# Buck_Power.net
KiCad netlist of a schematic drawn in Altium Designer
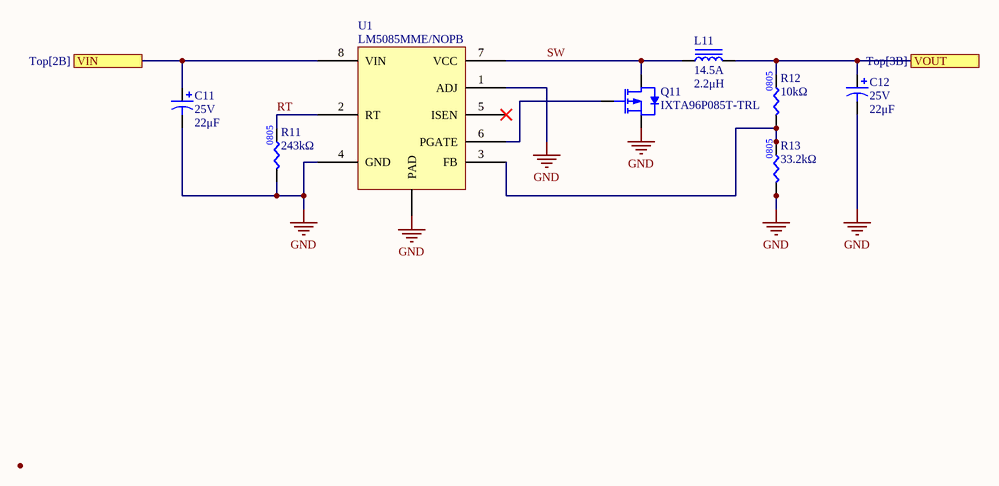
[diagram p0: Buck Power.SchDoc]

(export (version "E")
  (design (tool "Eeschema 10.0.6"))
  (components
    (comp (ref "C11")
      (value "22μF")
      (footprint "CAP2917")
      (description "CAP TANT 22UF 20% 25V 2917")
      (fields (field (name "VOLTAGE RATING") "25V") (field (name "Comment") "CAP_22uF_25V_TANT"))
      (libsource (lib "UWRT_Schematic_Library_2020") (part "CAP_22uF_25V_TANT"))
    )
    (comp (ref "C12")
      (value "22μF")
      (footprint "CAP2917")
      (description "CAP TANT 22UF 20% 25V 2917")
      (fields (field (name "VOLTAGE RATING") "25V") (field (name "Comment") "CAP_22uF_25V_TANT"))
      (libsource (lib "UWRT_Schematic_Library_2020") (part "CAP_22uF_25V_TANT"))
    )
    (comp (ref "L11")
      (value "IND_2.2uH_14.5A")
      (footprint "IND_VISHAY_IHLP3232DZER2R2M11")
      (description "INDUCTOR 2.2UH 14.5A 9.41 MOHM")
      (fields (field (name "CURRENT RATING") "14.5A") (field (name "INDUCTANCE") "2.2μH"))
      (libsource (lib "UWRT_Schematic_Library_2020") (part "IND_2.2uH_14.5A"))
    )
    (comp (ref "Q11")
      (value "PMOS_85V_96A")
      (footprint "D-PAK")
      (description "MOSFET P-CH 85V 96A TO263")
      (fields (field (name "MANUFACTURER PART NUMBER 1") "IXTA96P085T-TRL"))
      (libsource (lib "UWRT_Schematic_Library_2020") (part "PMOS_85V_96A"))
    )
    (comp (ref "R11")
      (value "243kΩ")
      (footprint "RES0805")
      (description "RES 243K OHM 1% 1/8W 0805")
      (fields (field (name "Comment") "RES_243kΩ_0805_1%"))
      (libsource (lib "UWRT_Schematic_Library_2020") (part "RES_243kΩ_0805_1%"))
    )
    (comp (ref "R12")
      (value "10kΩ")
      (footprint "RES0805")
      (description "RES 10K OHM 5% 1/8W 0805")
      (fields (field (name "LCSC PART #") "C17414") (field (name "Comment") "RES_10kΩ_0805_5%"))
      (libsource (lib "UWRT_Schematic_Library_2020") (part "RES_10kΩ_0805_5%"))
    )
    (comp (ref "R13")
      (value "33.2kΩ")
      (footprint "RES0805")
      (description "RES 33.2K OHM 1% 1/8W 0805")
      (fields (field (name "Comment") "RES_33.2kΩ_0805_1%"))
      (libsource (lib "UWRT_Schematic_Library_2020") (part "RES_33.2kΩ_0805_1%"))
    )
    (comp (ref "U1")
      (value "BUCK_LMR14050SDDAR")
      (footprint "8-VSSOP")
      (description "IC REG CTRLR BUCK 8VSSOP")
      (fields (field (name "MANUFACTURER PART NUMBER 1") "LM5085MME/NOPB"))
      (libsource (lib "UWRT_Schematic_Library_2020") (part "BUCK_LM5085"))
    )
  )
  (nets
    (net (code "1") (name "/RT") (class "Default")
      (node (ref "R11") (pin "2") (pinfunction "2_2") (pintype "passive"))
      (node (ref "U1") (pin "2") (pinfunction "RT_2") (pintype "passive"))
    )
    (net (code "2") (name "/SW") (class "Default")
      (node (ref "L11") (pin "1") (pinfunction "1_1") (pintype "passive"))
      (node (ref "Q11") (pin "1") (pinfunction "Drain_1") (pintype "passive"))
      (node (ref "U1") (pin "7") (pinfunction "VCC_7") (pintype "passive"))
    )
    (net (code "3") (name "/VIN") (class "Default")
      (node (ref "C11") (pin "1") (pinfunction "1_1") (pintype "passive"))
      (node (ref "U1") (pin "8") (pinfunction "VIN_8") (pintype "passive"))
    )
    (net (code "4") (name "/VOUT") (class "Default")
      (node (ref "C12") (pin "1") (pinfunction "1_1") (pintype "passive"))
      (node (ref "L11") (pin "2") (pinfunction "2_2") (pintype "passive"))
      (node (ref "R12") (pin "2") (pinfunction "2_2") (pintype "passive"))
    )
    (net (code "5") (name "GND") (class "Default")
      (node (ref "C11") (pin "2") (pinfunction "2_2") (pintype "passive"))
      (node (ref "C12") (pin "2") (pinfunction "2_2") (pintype "passive"))
      (node (ref "Q11") (pin "3") (pinfunction "Source_3") (pintype "passive"))
      (node (ref "R11") (pin "1") (pinfunction "1_1") (pintype "passive"))
      (node (ref "R13") (pin "1") (pinfunction "1_1") (pintype "passive"))
      (node (ref "U1") (pin "1") (pinfunction "ADJ_1") (pintype "passive"))
      (node (ref "U1") (pin "4") (pinfunction "GND_4") (pintype "passive"))
      (node (ref "U1") (pin "9") (pinfunction "PAD_9") (pintype "passive"))
    )
    (net (code "6") (name "Net-(Q11-Gate)") (class "Default")
      (node (ref "Q11") (pin "2") (pinfunction "Gate_2") (pintype "passive"))
      (node (ref "U1") (pin "6") (pinfunction "PGATE_6") (pintype "passive"))
    )
    (net (code "7") (name "Net-(U1-FB)") (class "Default")
      (node (ref "R12") (pin "1") (pinfunction "1_1") (pintype "passive"))
      (node (ref "R13") (pin "2") (pinfunction "2_2") (pintype "passive"))
      (node (ref "U1") (pin "3") (pinfunction "FB_3") (pintype "passive"))
    )
    (net (code "8") (name "unconnected-(U1-ISEN-Pad5)") (class "Default")
      (node (ref "U1") (pin "5") (pinfunction "ISEN_5") (pintype "passive+no_connect"))
    )
  )
)
